# 02-MCU_01.net
KiCad netlist of a schematic drawn in Altium Designer
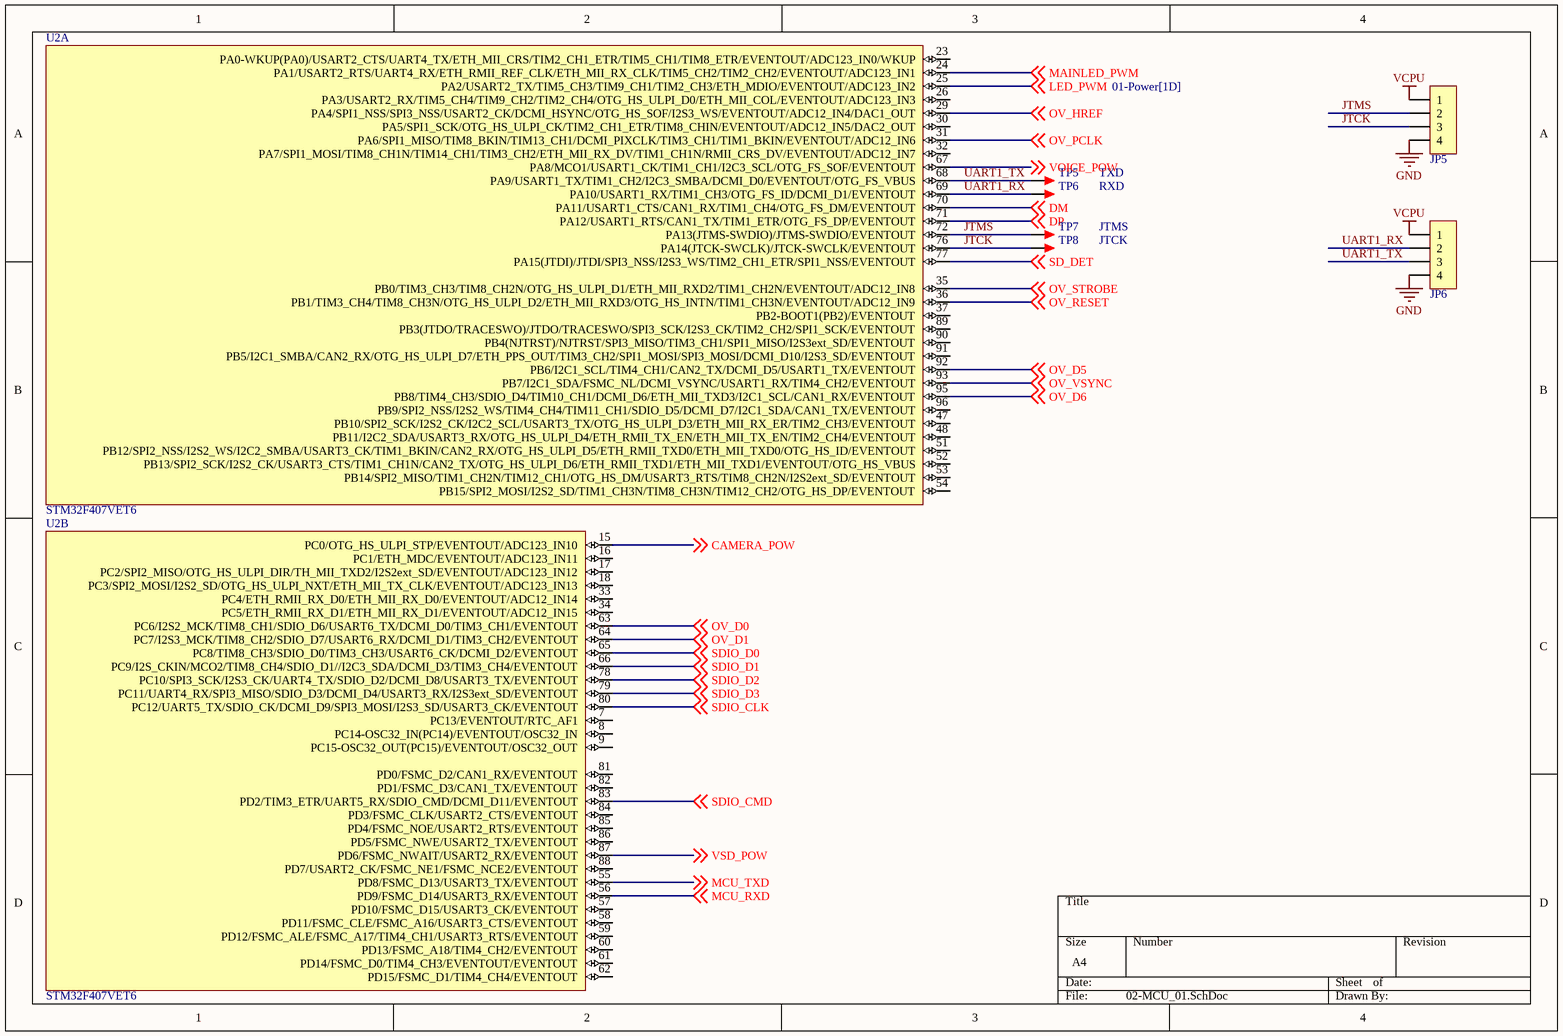
[diagram p0: 02-MCU_01.SchDoc]

(export (version "E")
  (design (tool "Eeschema 10.0.6"))
  (components
    (comp (ref "JP5")
      (value "HDR-1X4")
      (footprint "MX1.25-LT-4P")
      (description "4P连接器")
      (libsource (lib "5.1 - 1.25mm连接器(FPC1.25_GH1.25_MX1.25)") (part "Header 4"))
    )
    (comp (ref "JP6")
      (value "HDR-1X4")
      (footprint "MX1.25-LT-4P")
      (description "4P连接器")
      (libsource (lib "5.1 - 1.25mm连接器(FPC1.25_GH1.25_MX1.25)") (part "Header 4"))
    )
    (comp (ref "TP5")
      (value "TXD")
      (footprint "TEST 1.6")
      (description "测试点")
      (libsource (lib "0.5 - 按键_开关_蜂鸣器_电池_测试点_Mark点_铜柱") (part "TEST"))
    )
    (comp (ref "TP6")
      (value "RXD")
      (footprint "TEST 1.6")
      (description "测试点")
      (libsource (lib "0.5 - 按键_开关_蜂鸣器_电池_测试点_Mark点_铜柱") (part "TEST"))
    )
    (comp (ref "TP7")
      (value "JTMS")
      (footprint "TEST 1.6")
      (description "测试点")
      (libsource (lib "0.5 - 按键_开关_蜂鸣器_电池_测试点_Mark点_铜柱") (part "TEST"))
    )
    (comp (ref "TP8")
      (value "JTCK")
      (footprint "TEST 1.6")
      (description "测试点")
      (libsource (lib "0.5 - 按键_开关_蜂鸣器_电池_测试点_Mark点_铜柱") (part "TEST"))
    )
    (comp (ref "U2")
      (value "STM32F407VET6")
      (footprint "LQFP100_V")
      (libsource (lib "STM32 F4") (part "STM32F407VET6"))
    )
  )
  (nets
    (net (code "1") (name "/JTCK") (class "Default")
      (node (ref "JP5") (pin "3") (pinfunction "3_3") (pintype "passive"))
      (node (ref "TP8") (pin "1") (pinfunction "1_1") (pintype "passive"))
      (node (ref "U2") (pin "76") (pinfunction "PA14(JTCK-SWCLK)/JTCK-SWCLK/EVENTOUT_76") (pintype "bidirectional"))
    )
    (net (code "2") (name "/JTMS") (class "Default")
      (node (ref "JP5") (pin "2") (pinfunction "2_2") (pintype "passive"))
      (node (ref "TP7") (pin "1") (pinfunction "1_1") (pintype "passive"))
      (node (ref "U2") (pin "72") (pinfunction "PA13(JTMS-SWDIO)/JTMS-SWDIO/EVENTOUT_72") (pintype "bidirectional"))
    )
    (net (code "3") (name "/UART1_RX") (class "Default")
      (node (ref "JP6") (pin "2") (pinfunction "2_2") (pintype "passive"))
      (node (ref "TP6") (pin "1") (pinfunction "1_1") (pintype "passive"))
      (node (ref "U2") (pin "69") (pinfunction "PA10/USART1_RX/TIM1_CH3/OTG_FS_ID/DCMI_D1/EVENTOUT_69") (pintype "bidirectional"))
    )
    (net (code "4") (name "/UART1_TX") (class "Default")
      (node (ref "JP6") (pin "3") (pinfunction "3_3") (pintype "passive"))
      (node (ref "TP5") (pin "1") (pinfunction "1_1") (pintype "passive"))
      (node (ref "U2") (pin "68") (pinfunction "PA9/USART1_TX/TIM1_CH2/I2C3_SMBA/DCMI_D0/EVENTOUT/OTG_FS_VBUS_68") (pintype "bidirectional"))
    )
    (net (code "5") (name "CAMERA_POW") (class "Default")
      (node (ref "U2") (pin "15") (pinfunction "PC0/OTG_HS_ULPI_STP/EVENTOUT/ADC123_IN10_15") (pintype "bidirectional"))
    )
    (net (code "6") (name "DM") (class "Default")
      (node (ref "U2") (pin "70") (pinfunction "PA11/USART1_CTS/CAN1_RX/TIM1_CH4/OTG_FS_DM/EVENTOUT_70") (pintype "bidirectional"))
    )
    (net (code "7") (name "DP") (class "Default")
      (node (ref "U2") (pin "71") (pinfunction "PA12/USART1_RTS/CAN1_TX/TIM1_ETR/OTG_FS_DP/EVENTOUT_71") (pintype "bidirectional"))
    )
    (net (code "8") (name "GND") (class "Default")
      (node (ref "JP5") (pin "4") (pinfunction "4_4") (pintype "passive"))
      (node (ref "JP6") (pin "4") (pinfunction "4_4") (pintype "passive"))
    )
    (net (code "9") (name "LED_PWM") (class "Default")
      (node (ref "U2") (pin "25") (pinfunction "PA2/USART2_TX/TIM5_CH3/TIM9_CH1/TIM2_CH3/ETH_MDIO/EVENTOUT/ADC123_IN2_25") (pintype "bidirectional"))
    )
    (net (code "10") (name "MAINLED_PWM") (class "Default")
      (node (ref "U2") (pin "24") (pinfunction "PA1/USART2_RTS/UART4_RX/ETH_RMII_REF_CLK/ETH_MII_RX_CLK/TIM5_CH2/TIM2_CH2/EVENTOUT/ADC123_IN1_24") (pintype "bidirectional"))
    )
    (net (code "11") (name "MCU_RXD") (class "Default")
      (node (ref "U2") (pin "56") (pinfunction "PD9/FSMC_D14/USART3_RX/EVENTOUT_56") (pintype "bidirectional"))
    )
    (net (code "12") (name "MCU_TXD") (class "Default")
      (node (ref "U2") (pin "55") (pinfunction "PD8/FSMC_D13/USART3_TX/EVENTOUT_55") (pintype "bidirectional"))
    )
    (net (code "13") (name "OV_D0") (class "Default")
      (node (ref "U2") (pin "63") (pinfunction "PC6/I2S2_MCK/TIM8_CH1/SDIO_D6/USART6_TX/DCMI_D0/TIM3_CH1/EVENTOUT_63") (pintype "bidirectional"))
    )
    (net (code "14") (name "OV_D1") (class "Default")
      (node (ref "U2") (pin "64") (pinfunction "PC7/I2S3_MCK/TIM8_CH2/SDIO_D7/USART6_RX/DCMI_D1/TIM3_CH2/EVENTOUT_64") (pintype "bidirectional"))
    )
    (net (code "15") (name "OV_D5") (class "Default")
      (node (ref "U2") (pin "92") (pinfunction "PB6/I2C1_SCL/TIM4_CH1/CAN2_TX/DCMI_D5/USART1_TX/EVENTOUT_92") (pintype "bidirectional"))
    )
    (net (code "16") (name "OV_D6") (class "Default")
      (node (ref "U2") (pin "95") (pinfunction "PB8/TIM4_CH3/SDIO_D4/TIM10_CH1/DCMI_D6/ETH_MII_TXD3/I2C1_SCL/CAN1_RX/EVENTOUT_95") (pintype "bidirectional"))
    )
    (net (code "17") (name "OV_HREF") (class "Default")
      (node (ref "U2") (pin "29") (pinfunction "PA4/SPI1_NSS/SPI3_NSS/USART2_CK/DCMI_HSYNC/OTG_HS_SOF/I2S3_WS/EVENTOUT/ADC12_IN4/DAC1_OUT_29") (pintype "bidirectional"))
    )
    (net (code "18") (name "OV_PCLK") (class "Default")
      (node (ref "U2") (pin "31") (pinfunction "PA6/SPI1_MISO/TIM8_BKIN/TIM13_CH1/DCMI_PIXCLK/TIM3_CH1/TIM1_BKIN/EVENTOUT/ADC12_IN6_31") (pintype "bidirectional"))
    )
    (net (code "19") (name "OV_RESET") (class "Default")
      (node (ref "U2") (pin "36") (pinfunction "PB1/TIM3_CH4/TIM8_CH3N/OTG_HS_ULPI_D2/ETH_MII_RXD3/OTG_HS_INTN/TIM1_CH3N/EVENTOUT/ADC12_IN9_36") (pintype "bidirectional"))
    )
    (net (code "20") (name "OV_STROBE") (class "Default")
      (node (ref "U2") (pin "35") (pinfunction "PB0/TIM3_CH3/TIM8_CH2N/OTG_HS_ULPI_D1/ETH_MII_RXD2/TIM1_CH2N/EVENTOUT/ADC12_IN8_35") (pintype "bidirectional"))
    )
    (net (code "21") (name "OV_VSYNC") (class "Default")
      (node (ref "U2") (pin "93") (pinfunction "PB7/I2C1_SDA/FSMC_NL/DCMI_VSYNC/USART1_RX/TIM4_CH2/EVENTOUT_93") (pintype "bidirectional"))
    )
    (net (code "22") (name "SDIO_CLK") (class "Default")
      (node (ref "U2") (pin "80") (pinfunction "PC12/UART5_TX/SDIO_CK/DCMI_D9/SPI3_MOSI/I2S3_SD/USART3_CK/EVENTOUT_80") (pintype "bidirectional"))
    )
    (net (code "23") (name "SDIO_CMD") (class "Default")
      (node (ref "U2") (pin "83") (pinfunction "PD2/TIM3_ETR/UART5_RX/SDIO_CMD/DCMI_D11/EVENTOUT_83") (pintype "bidirectional"))
    )
    (net (code "24") (name "SDIO_D0") (class "Default")
      (node (ref "U2") (pin "65") (pinfunction "PC8/TIM8_CH3/SDIO_D0/TIM3_CH3/USART6_CK/DCMI_D2/EVENTOUT_65") (pintype "bidirectional"))
    )
    (net (code "25") (name "SDIO_D1") (class "Default")
      (node (ref "U2") (pin "66") (pinfunction "PC9/I2S_CKIN/MCO2/TIM8_CH4/SDIO_D1//I2C3_SDA/DCMI_D3/TIM3_CH4/EVENTOUT_66") (pintype "bidirectional"))
    )
    (net (code "26") (name "SDIO_D2") (class "Default")
      (node (ref "U2") (pin "78") (pinfunction "PC10/SPI3_SCK/I2S3_CK/UART4_TX/SDIO_D2/DCMI_D8/USART3_TX/EVENTOUT_78") (pintype "bidirectional"))
    )
    (net (code "27") (name "SDIO_D3") (class "Default")
      (node (ref "U2") (pin "79") (pinfunction "PC11/UART4_RX/SPI3_MISO/SDIO_D3/DCMI_D4/USART3_RX/I2S3ext_SD/EVENTOUT_79") (pintype "bidirectional"))
    )
    (net (code "28") (name "SD_DET") (class "Default")
      (node (ref "U2") (pin "77") (pinfunction "PA15(JTDI)/JTDI/SPI3_NSS/I2S3_WS/TIM2_CH1_ETR/SPI1_NSS/EVENTOUT_77") (pintype "bidirectional"))
    )
    (net (code "29") (name "VCPU") (class "Default")
      (node (ref "JP5") (pin "1") (pinfunction "1_1") (pintype "passive"))
      (node (ref "JP6") (pin "1") (pinfunction "1_1") (pintype "passive"))
    )
    (net (code "30") (name "VOICE_POW") (class "Default")
      (node (ref "U2") (pin "67") (pinfunction "PA8/MCO1/USART1_CK/TIM1_CH1/I2C3_SCL/OTG_FS_SOF/EVENTOUT_67") (pintype "bidirectional"))
    )
    (net (code "31") (name "VSD_POW") (class "Default")
      (node (ref "U2") (pin "87") (pinfunction "PD6/FSMC_NWAIT/USART2_RX/EVENTOUT_87") (pintype "bidirectional"))
    )
    (net (code "32") (name "unconnected-(U2A-PA0-WKUP(PA0){slash}USART2_CTS{slash}UART4_TX{slash}ETH_MII_CRS{slash}TIM2_CH1_ETR{slash}TIM5_CH1{slash}TIM8_ETR{slash}EVENTOUT{slash}ADC123_IN0{slash}WKUP-Pad23)") (class "Default")
      (node (ref "U2") (pin "23") (pinfunction "PA0-WKUP(PA0)/USART2_CTS/UART4_TX/ETH_MII_CRS/TIM2_CH1_ETR/TIM5_CH1/TIM8_ETR/EVENTOUT/ADC123_IN0/WKUP_23") (pintype "bidirectional"))
    )
    (net (code "33") (name "unconnected-(U2A-PA3{slash}USART2_RX{slash}TIM5_CH4{slash}TIM9_CH2{slash}TIM2_CH4{slash}OTG_HS_ULPI_D0{slash}ETH_MII_COL{slash}EVENTOUT{slash}ADC123_IN3-Pad26)") (class "Default")
      (node (ref "U2") (pin "26") (pinfunction "PA3/USART2_RX/TIM5_CH4/TIM9_CH2/TIM2_CH4/OTG_HS_ULPI_D0/ETH_MII_COL/EVENTOUT/ADC123_IN3_26") (pintype "bidirectional"))
    )
    (net (code "34") (name "unconnected-(U2A-PA5{slash}SPI1_SCK{slash}OTG_HS_ULPI_CK{slash}TIM2_CH1_ETR{slash}TIM8_CHIN{slash}EVENTOUT{slash}ADC12_IN5{slash}DAC2_OUT-Pad30)") (class "Default")
      (node (ref "U2") (pin "30") (pinfunction "PA5/SPI1_SCK/OTG_HS_ULPI_CK/TIM2_CH1_ETR/TIM8_CHIN/EVENTOUT/ADC12_IN5/DAC2_OUT_30") (pintype "bidirectional"))
    )
    (net (code "35") (name "unconnected-(U2A-PA7{slash}SPI1_MOSI{slash}TIM8_CH1N{slash}TIM14_CH1{slash}TIM3_CH2{slash}ETH_MII_RX_DV{slash}TIM1_CH1N{slash}RMII_CRS_DV{slash}EVENTOUT{slash}ADC12_IN7-Pad32)") (class "Default")
      (node (ref "U2") (pin "32") (pinfunction "PA7/SPI1_MOSI/TIM8_CH1N/TIM14_CH1/TIM3_CH2/ETH_MII_RX_DV/TIM1_CH1N/RMII_CRS_DV/EVENTOUT/ADC12_IN7_32") (pintype "bidirectional"))
    )
    (net (code "36") (name "unconnected-(U2A-PB2-BOOT1(PB2){slash}EVENTOUT-Pad37)") (class "Default")
      (node (ref "U2") (pin "37") (pinfunction "PB2-BOOT1(PB2)/EVENTOUT_37") (pintype "bidirectional"))
    )
    (net (code "37") (name "unconnected-(U2A-PB3(JTDO{slash}TRACESWO){slash}JTDO{slash}TRACESWO{slash}SPI3_SCK{slash}I2S3_CK{slash}TIM2_CH2{slash}SPI1_SCK{slash}EVENTOUT-Pad89)") (class "Default")
      (node (ref "U2") (pin "89") (pinfunction "PB3(JTDO/TRACESWO)/JTDO/TRACESWO/SPI3_SCK/I2S3_CK/TIM2_CH2/SPI1_SCK/EVENTOUT_89") (pintype "bidirectional"))
    )
    (net (code "38") (name "unconnected-(U2A-PB4(NJTRST){slash}NJTRST{slash}SPI3_MISO{slash}TIM3_CH1{slash}SPI1_MISO{slash}I2S3ext_SD{slash}EVENTOUT-Pad90)") (class "Default")
      (node (ref "U2") (pin "90") (pinfunction "PB4(NJTRST)/NJTRST/SPI3_MISO/TIM3_CH1/SPI1_MISO/I2S3ext_SD/EVENTOUT_90") (pintype "bidirectional"))
    )
    (net (code "39") (name "unconnected-(U2A-PB5{slash}I2C1_SMBA{slash}CAN2_RX{slash}OTG_HS_ULPI_D7{slash}ETH_PPS_OUT{slash}TIM3_CH2{slash}SPI1_MOSI{slash}SPI3_MOSI{slash}DCMI_D10{slash}I2S3_SD{slash}EVENTOUT-Pad91)") (class "Default")
      (node (ref "U2") (pin "91") (pinfunction "PB5/I2C1_SMBA/CAN2_RX/OTG_HS_ULPI_D7/ETH_PPS_OUT/TIM3_CH2/SPI1_MOSI/SPI3_MOSI/DCMI_D10/I2S3_SD/EVENTOUT_91") (pintype "bidirectional"))
    )
    (net (code "40") (name "unconnected-(U2A-PB9{slash}SPI2_NSS{slash}I2S2_WS{slash}TIM4_CH4{slash}TIM11_CH1{slash}SDIO_D5{slash}DCMI_D7{slash}I2C1_SDA{slash}CAN1_TX{slash}EVENTOUT-Pad96)") (class "Default")
      (node (ref "U2") (pin "96") (pinfunction "PB9/SPI2_NSS/I2S2_WS/TIM4_CH4/TIM11_CH1/SDIO_D5/DCMI_D7/I2C1_SDA/CAN1_TX/EVENTOUT_96") (pintype "bidirectional"))
    )
    (net (code "41") (name "unconnected-(U2A-PB10{slash}SPI2_SCK{slash}I2S2_CK{slash}I2C2_SCL{slash}USART3_TX{slash}OTG_HS_ULPI_D3{slash}ETH_MII_RX_ER{slash}TIM2_CH3{slash}EVENTOUT-Pad47)") (class "Default")
      (node (ref "U2") (pin "47") (pinfunction "PB10/SPI2_SCK/I2S2_CK/I2C2_SCL/USART3_TX/OTG_HS_ULPI_D3/ETH_MII_RX_ER/TIM2_CH3/EVENTOUT_47") (pintype "bidirectional"))
    )
    (net (code "42") (name "unconnected-(U2A-PB11{slash}I2C2_SDA{slash}USART3_RX{slash}OTG_HS_ULPI_D4{slash}ETH_RMII_TX_EN{slash}ETH_MII_TX_EN{slash}TIM2_CH4{slash}EVENTOUT-Pad48)") (class "Default")
      (node (ref "U2") (pin "48") (pinfunction "PB11/I2C2_SDA/USART3_RX/OTG_HS_ULPI_D4/ETH_RMII_TX_EN/ETH_MII_TX_EN/TIM2_CH4/EVENTOUT_48") (pintype "bidirectional"))
    )
    (net (code "43") (name "unconnected-(U2A-PB12{slash}SPI2_NSS{slash}I2S2_WS{slash}I2C2_SMBA{slash}USART3_CK{slash}TIM1_BKIN{slash}CAN2_RX{slash}OTG_HS_ULPI_D5{slash}ETH_RMII_TXD0{slash}ETH_MII_TXD0{slash}OTG_HS_ID{slash}EVENTOUT-Pad51)") (class "Default")
      (node (ref "U2") (pin "51") (pinfunction "PB12/SPI2_NSS/I2S2_WS/I2C2_SMBA/USART3_CK/TIM1_BKIN/CAN2_RX/OTG_HS_ULPI_D5/ETH_RMII_TXD0/ETH_MII_TXD0/OTG_HS_ID/EVENTOUT_51") (pintype "bidirectional"))
    )
    (net (code "44") (name "unconnected-(U2A-PB13{slash}SPI2_SCK{slash}I2S2_CK{slash}USART3_CTS{slash}TIM1_CH1N{slash}CAN2_TX{slash}OTG_HS_ULPI_D6{slash}ETH_RMII_TXD1{slash}ETH_MII_TXD1{slash}EVENTOUT{slash}OTG_HS_VBUS-Pad52)") (class "Default")
      (node (ref "U2") (pin "52") (pinfunction "PB13/SPI2_SCK/I2S2_CK/USART3_CTS/TIM1_CH1N/CAN2_TX/OTG_HS_ULPI_D6/ETH_RMII_TXD1/ETH_MII_TXD1/EVENTOUT/OTG_HS_VBUS_52") (pintype "bidirectional"))
    )
    (net (code "45") (name "unconnected-(U2A-PB14{slash}SPI2_MISO{slash}TIM1_CH2N{slash}TIM12_CH1{slash}OTG_HS_DM{slash}USART3_RTS{slash}TIM8_CH2N{slash}I2S2ext_SD{slash}EVENTOUT-Pad53)") (class "Default")
      (node (ref "U2") (pin "53") (pinfunction "PB14/SPI2_MISO/TIM1_CH2N/TIM12_CH1/OTG_HS_DM/USART3_RTS/TIM8_CH2N/I2S2ext_SD/EVENTOUT_53") (pintype "bidirectional"))
    )
    (net (code "46") (name "unconnected-(U2A-PB15{slash}SPI2_MOSI{slash}I2S2_SD{slash}TIM1_CH3N{slash}TIM8_CH3N{slash}TIM12_CH2{slash}OTG_HS_DP{slash}EVENTOUT-Pad54)") (class "Default")
      (node (ref "U2") (pin "54") (pinfunction "PB15/SPI2_MOSI/I2S2_SD/TIM1_CH3N/TIM8_CH3N/TIM12_CH2/OTG_HS_DP/EVENTOUT_54") (pintype "bidirectional"))
    )
    (net (code "47") (name "unconnected-(U2B-PC1{slash}ETH_MDC{slash}EVENTOUT{slash}ADC123_IN11-Pad16)") (class "Default")
      (node (ref "U2") (pin "16") (pinfunction "PC1/ETH_MDC/EVENTOUT/ADC123_IN11_16") (pintype "bidirectional"))
    )
    (net (code "48") (name "unconnected-(U2B-PC2{slash}SPI2_MISO{slash}OTG_HS_ULPI_DIR{slash}TH_MII_TXD2{slash}I2S2ext_SD{slash}EVENTOUT{slash}ADC123_IN12-Pad17)") (class "Default")
      (node (ref "U2") (pin "17") (pinfunction "PC2/SPI2_MISO/OTG_HS_ULPI_DIR/TH_MII_TXD2/I2S2ext_SD/EVENTOUT/ADC123_IN12_17") (pintype "bidirectional"))
    )
    (net (code "49") (name "unconnected-(U2B-PC3{slash}SPI2_MOSI{slash}I2S2_SD{slash}OTG_HS_ULPI_NXT{slash}ETH_MII_TX_CLK{slash}EVENTOUT{slash}ADC123_IN13-Pad18)") (class "Default")
      (node (ref "U2") (pin "18") (pinfunction "PC3/SPI2_MOSI/I2S2_SD/OTG_HS_ULPI_NXT/ETH_MII_TX_CLK/EVENTOUT/ADC123_IN13_18") (pintype "bidirectional"))
    )
    (net (code "50") (name "unconnected-(U2B-PC4{slash}ETH_RMII_RX_D0{slash}ETH_MII_RX_D0{slash}EVENTOUT{slash}ADC12_IN14-Pad33)") (class "Default")
      (node (ref "U2") (pin "33") (pinfunction "PC4/ETH_RMII_RX_D0/ETH_MII_RX_D0/EVENTOUT/ADC12_IN14_33") (pintype "bidirectional"))
    )
    (net (code "51") (name "unconnected-(U2B-PC5{slash}ETH_RMII_RX_D1{slash}ETH_MII_RX_D1{slash}EVENTOUT{slash}ADC12_IN15-Pad34)") (class "Default")
      (node (ref "U2") (pin "34") (pinfunction "PC5/ETH_RMII_RX_D1/ETH_MII_RX_D1/EVENTOUT/ADC12_IN15_34") (pintype "bidirectional"))
    )
    (net (code "52") (name "unconnected-(U2B-PC13{slash}EVENTOUT{slash}RTC_AF1-Pad7)") (class "Default")
      (node (ref "U2") (pin "7") (pinfunction "PC13/EVENTOUT/RTC_AF1_7") (pintype "bidirectional"))
    )
    (net (code "53") (name "unconnected-(U2B-PC14-OSC32_IN(PC14){slash}EVENTOUT{slash}OSC32_IN-Pad8)") (class "Default")
      (node (ref "U2") (pin "8") (pinfunction "PC14-OSC32_IN(PC14)/EVENTOUT/OSC32_IN_8") (pintype "bidirectional"))
    )
    (net (code "54") (name "unconnected-(U2B-PC15-OSC32_OUT(PC15){slash}EVENTOUT{slash}OSC32_OUT-Pad9)") (class "Default")
      (node (ref "U2") (pin "9") (pinfunction "PC15-OSC32_OUT(PC15)/EVENTOUT/OSC32_OUT_9") (pintype "bidirectional"))
    )
    (net (code "55") (name "unconnected-(U2B-PD0{slash}FSMC_D2{slash}CAN1_RX{slash}EVENTOUT-Pad81)") (class "Default")
      (node (ref "U2") (pin "81") (pinfunction "PD0/FSMC_D2/CAN1_RX/EVENTOUT_81") (pintype "bidirectional"))
    )
    (net (code "56") (name "unconnected-(U2B-PD1{slash}FSMC_D3{slash}CAN1_TX{slash}EVENTOUT-Pad82)") (class "Default")
      (node (ref "U2") (pin "82") (pinfunction "PD1/FSMC_D3/CAN1_TX/EVENTOUT_82") (pintype "bidirectional"))
    )
    (net (code "57") (name "unconnected-(U2B-PD3{slash}FSMC_CLK{slash}USART2_CTS{slash}EVENTOUT-Pad84)") (class "Default")
      (node (ref "U2") (pin "84") (pinfunction "PD3/FSMC_CLK/USART2_CTS/EVENTOUT_84") (pintype "bidirectional"))
    )
    (net (code "58") (name "unconnected-(U2B-PD4{slash}FSMC_NOE{slash}USART2_RTS{slash}EVENTOUT-Pad85)") (class "Default")
      (node (ref "U2") (pin "85") (pinfunction "PD4/FSMC_NOE/USART2_RTS/EVENTOUT_85") (pintype "bidirectional"))
    )
    (net (code "59") (name "unconnected-(U2B-PD5{slash}FSMC_NWE{slash}USART2_TX{slash}EVENTOUT-Pad86)") (class "Default")
      (node (ref "U2") (pin "86") (pinfunction "PD5/FSMC_NWE/USART2_TX/EVENTOUT_86") (pintype "bidirectional"))
    )
    (net (code "60") (name "unconnected-(U2B-PD7{slash}USART2_CK{slash}FSMC_NE1{slash}FSMC_NCE2{slash}EVENTOUT-Pad88)") (class "Default")
      (node (ref "U2") (pin "88") (pinfunction "PD7/USART2_CK/FSMC_NE1/FSMC_NCE2/EVENTOUT_88") (pintype "bidirectional"))
    )
    (net (code "61") (name "unconnected-(U2B-PD10{slash}FSMC_D15{slash}USART3_CK{slash}EVENTOUT-Pad57)") (class "Default")
      (node (ref "U2") (pin "57") (pinfunction "PD10/FSMC_D15/USART3_CK/EVENTOUT_57") (pintype "bidirectional"))
    )
    (net (code "62") (name "unconnected-(U2B-PD11{slash}FSMC_CLE{slash}FSMC_A16{slash}USART3_CTS{slash}EVENTOUT-Pad58)") (class "Default")
      (node (ref "U2") (pin "58") (pinfunction "PD11/FSMC_CLE/FSMC_A16/USART3_CTS/EVENTOUT_58") (pintype "bidirectional"))
    )
    (net (code "63") (name "unconnected-(U2B-PD12{slash}FSMC_ALE{slash}FSMC_A17{slash}TIM4_CH1{slash}USART3_RTS{slash}EVENTOUT-Pad59)") (class "Default")
      (node (ref "U2") (pin "59") (pinfunction "PD12/FSMC_ALE/FSMC_A17/TIM4_CH1/USART3_RTS/EVENTOUT_59") (pintype "bidirectional"))
    )
    (net (code "64") (name "unconnected-(U2B-PD13{slash}FSMC_A18{slash}TIM4_CH2{slash}EVENTOUT-Pad60)") (class "Default")
      (node (ref "U2") (pin "60") (pinfunction "PD13/FSMC_A18/TIM4_CH2/EVENTOUT_60") (pintype "bidirectional"))
    )
    (net (code "65") (name "unconnected-(U2B-PD14{slash}FSMC_D0{slash}TIM4_CH3{slash}EVENTOUT{slash}EVENTOUT-Pad61)") (class "Default")
      (node (ref "U2") (pin "61") (pinfunction "PD14/FSMC_D0/TIM4_CH3/EVENTOUT/EVENTOUT_61") (pintype "bidirectional"))
    )
    (net (code "66") (name "unconnected-(U2B-PD15{slash}FSMC_D1{slash}TIM4_CH4{slash}EVENTOUT-Pad62)") (class "Default")
      (node (ref "U2") (pin "62") (pinfunction "PD15/FSMC_D1/TIM4_CH4/EVENTOUT_62") (pintype "bidirectional"))
    )
  )
)
